# v2.net
KiCad netlist of a schematic drawn in EAGLE
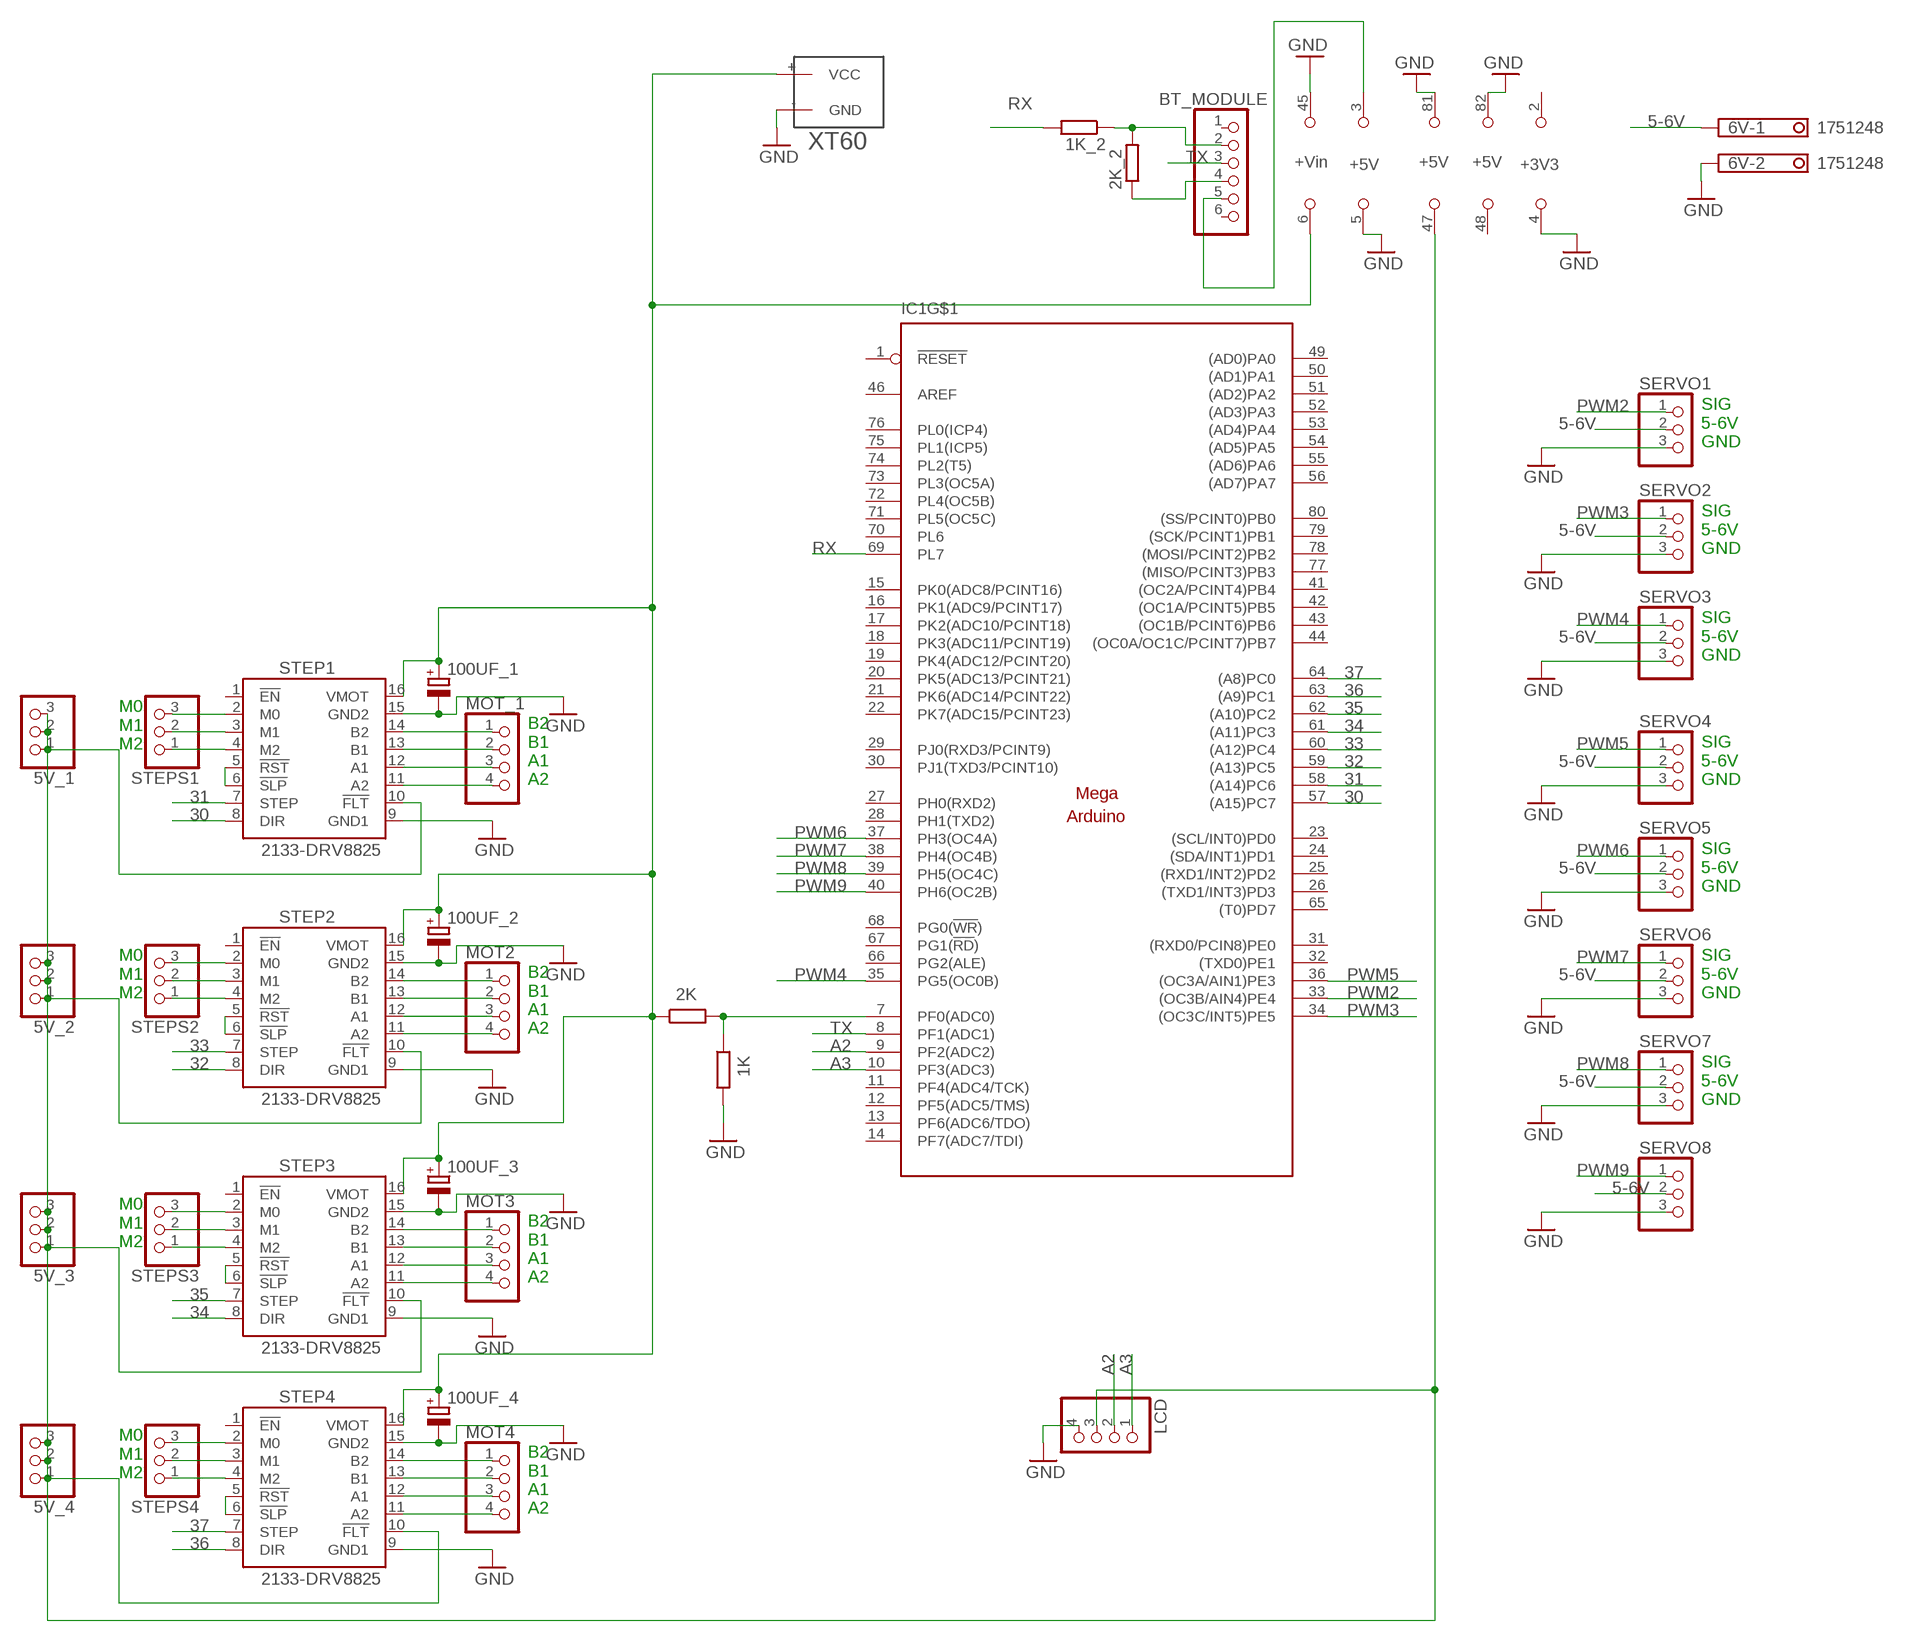
[diagram p0: schematic, sheet 1]

(export (version "E")
  (design (tool "Eeschema 10.0.6"))
  (components
    (comp (ref "1K")
      (value "R-EU_0204/7")
      (footprint "eagle-import:0204_7")
      (libsource (lib "eagle-import") (part "R-EU_0204/7"))
    )
    (comp (ref "1K_2")
      (value "R-EU_0204/7")
      (footprint "eagle-import:0204_7")
      (libsource (lib "eagle-import") (part "R-EU_0204/7"))
    )
    (comp (ref "2K")
      (value "R-EU_0204/7")
      (footprint "eagle-import:0204_7")
      (libsource (lib "eagle-import") (part "R-EU_0204/7"))
    )
    (comp (ref "2K_2")
      (value "R-EU_0204/7")
      (footprint "eagle-import:0204_7")
      (libsource (lib "eagle-import") (part "R-EU_0204/7"))
    )
    (comp (ref "5V_1")
      (value "PINHD-1X3")
      (footprint "eagle-import:1X03")
      (libsource (lib "eagle-import") (part "PINHD-1X3"))
    )
    (comp (ref "5V_2")
      (value "PINHD-1X3")
      (footprint "eagle-import:1X03")
      (libsource (lib "eagle-import") (part "PINHD-1X3"))
    )
    (comp (ref "5V_3")
      (value "PINHD-1X3")
      (footprint "eagle-import:1X03")
      (libsource (lib "eagle-import") (part "PINHD-1X3"))
    )
    (comp (ref "5V_4")
      (value "PINHD-1X3")
      (footprint "eagle-import:1X03")
      (libsource (lib "eagle-import") (part "PINHD-1X3"))
    )
    (comp (ref "6V")
      (value "1751248")
      (footprint "eagle-import:1751248")
      (libsource (lib "eagle-import") (part "1751248"))
    )
    (comp (ref "100UF_1")
      (value "CPOL-EUE5-5")
      (footprint "eagle-import:E5-5")
      (libsource (lib "eagle-import") (part "CPOL-EUE5-5"))
    )
    (comp (ref "100UF_2")
      (value "CPOL-EUE5-5")
      (footprint "eagle-import:E5-5")
      (libsource (lib "eagle-import") (part "CPOL-EUE5-5"))
    )
    (comp (ref "100UF_3")
      (value "CPOL-EUE5-5")
      (footprint "eagle-import:E5-5")
      (libsource (lib "eagle-import") (part "CPOL-EUE5-5"))
    )
    (comp (ref "100UF_4")
      (value "CPOL-EUE5-5")
      (footprint "eagle-import:E5-5")
      (libsource (lib "eagle-import") (part "CPOL-EUE5-5"))
    )
    (comp (ref "BT_MODULE")
      (value "PINHD-1X6")
      (footprint "eagle-import:1X06")
      (libsource (lib "eagle-import") (part "PINHD-1X6"))
    )
    (comp (ref "IC1")
      (value "MEGAARDUINO_22")
      (footprint "eagle-import:MEGA_ARDUINO_2")
      (libsource (lib "eagle-import") (part "MEGAARDUINO_22"))
    )
    (comp (ref "LCD")
      (value "PINHD-1X4")
      (footprint "eagle-import:1X04")
      (libsource (lib "eagle-import") (part "PINHD-1X4"))
    )
    (comp (ref "MOT2")
      (value "PINHD-1X4")
      (footprint "eagle-import:1X04")
      (libsource (lib "eagle-import") (part "PINHD-1X4"))
    )
    (comp (ref "MOT3")
      (value "PINHD-1X4")
      (footprint "eagle-import:1X04")
      (libsource (lib "eagle-import") (part "PINHD-1X4"))
    )
    (comp (ref "MOT4")
      (value "PINHD-1X4")
      (footprint "eagle-import:1X04")
      (libsource (lib "eagle-import") (part "PINHD-1X4"))
    )
    (comp (ref "MOT_1")
      (value "PINHD-1X4")
      (footprint "eagle-import:1X04")
      (libsource (lib "eagle-import") (part "PINHD-1X4"))
    )
    (comp (ref "SERVO1")
      (value "PINHD-1X3")
      (footprint "eagle-import:1X03")
      (libsource (lib "eagle-import") (part "PINHD-1X3"))
    )
    (comp (ref "SERVO2")
      (value "PINHD-1X3")
      (footprint "eagle-import:1X03")
      (libsource (lib "eagle-import") (part "PINHD-1X3"))
    )
    (comp (ref "SERVO3")
      (value "PINHD-1X3")
      (footprint "eagle-import:1X03")
      (libsource (lib "eagle-import") (part "PINHD-1X3"))
    )
    (comp (ref "SERVO4")
      (value "PINHD-1X3")
      (footprint "eagle-import:1X03")
      (libsource (lib "eagle-import") (part "PINHD-1X3"))
    )
    (comp (ref "SERVO5")
      (value "PINHD-1X3")
      (footprint "eagle-import:1X03")
      (libsource (lib "eagle-import") (part "PINHD-1X3"))
    )
    (comp (ref "SERVO6")
      (value "PINHD-1X3")
      (footprint "eagle-import:1X03")
      (libsource (lib "eagle-import") (part "PINHD-1X3"))
    )
    (comp (ref "SERVO7")
      (value "PINHD-1X3")
      (footprint "eagle-import:1X03")
      (libsource (lib "eagle-import") (part "PINHD-1X3"))
    )
    (comp (ref "SERVO8")
      (value "PINHD-1X3")
      (footprint "eagle-import:1X03")
      (libsource (lib "eagle-import") (part "PINHD-1X3"))
    )
    (comp (ref "STEP1")
      (value "2133-DRV8825")
      (footprint "eagle-import:DRV8825")
      (libsource (lib "eagle-import") (part "2133-DRV8825"))
    )
    (comp (ref "STEP2")
      (value "2133-DRV8825")
      (footprint "eagle-import:DRV8825")
      (libsource (lib "eagle-import") (part "2133-DRV8825"))
    )
    (comp (ref "STEP3")
      (value "2133-DRV8825")
      (footprint "eagle-import:DRV8825")
      (libsource (lib "eagle-import") (part "2133-DRV8825"))
    )
    (comp (ref "STEP4")
      (value "2133-DRV8825")
      (footprint "eagle-import:DRV8825")
      (libsource (lib "eagle-import") (part "2133-DRV8825"))
    )
    (comp (ref "STEPS1")
      (value "PINHD-1X3")
      (footprint "eagle-import:1X03")
      (libsource (lib "eagle-import") (part "PINHD-1X3"))
    )
    (comp (ref "STEPS2")
      (value "PINHD-1X3")
      (footprint "eagle-import:1X03")
      (libsource (lib "eagle-import") (part "PINHD-1X3"))
    )
    (comp (ref "STEPS3")
      (value "PINHD-1X3")
      (footprint "eagle-import:1X03")
      (libsource (lib "eagle-import") (part "PINHD-1X3"))
    )
    (comp (ref "STEPS4")
      (value "PINHD-1X3")
      (footprint "eagle-import:1X03")
      (libsource (lib "eagle-import") (part "PINHD-1X3"))
    )
    (comp (ref "U$1")
      (value "XT60")
      (footprint "eagle-import:XT60")
      (libsource (lib "eagle-import") (part "XT60"))
    )
  )
  (nets
    (net (code "1") (name "/+3V3") (class "Default")
      (node (ref "IC1") (pin "2") (pinfunction "+3V3_2") (pintype "power_in"))
    )
    (net (code "2") (name "/+5V") (class "Default")
      (node (ref "IC1") (pin "48") (pinfunction "+5V_48") (pintype "power_in"))
    )
    (net (code "3") (name "/5-6V") (class "Default")
      (node (ref "6V") (pin "1") (pinfunction "K_1") (pintype "passive"))
      (node (ref "SERVO1") (pin "2") (pinfunction "2_2") (pintype "passive"))
      (node (ref "SERVO2") (pin "2") (pinfunction "2_2") (pintype "passive"))
      (node (ref "SERVO3") (pin "2") (pinfunction "2_2") (pintype "passive"))
      (node (ref "SERVO4") (pin "2") (pinfunction "2_2") (pintype "passive"))
      (node (ref "SERVO5") (pin "2") (pinfunction "2_2") (pintype "passive"))
      (node (ref "SERVO6") (pin "2") (pinfunction "2_2") (pintype "passive"))
      (node (ref "SERVO7") (pin "2") (pinfunction "2_2") (pintype "passive"))
      (node (ref "SERVO8") (pin "2") (pinfunction "2_2") (pintype "passive"))
    )
    (net (code "4") (name "/30") (class "Default")
      (node (ref "IC1") (pin "57") (pinfunction "(A15)PC7_57") (pintype "bidirectional"))
      (node (ref "STEP1") (pin "8") (pinfunction "DIR_8") (pintype "input"))
    )
    (net (code "5") (name "/31") (class "Default")
      (node (ref "IC1") (pin "58") (pinfunction "(A14)PC6_58") (pintype "bidirectional"))
      (node (ref "STEP1") (pin "7") (pinfunction "STEP_7") (pintype "input"))
    )
    (net (code "6") (name "/32") (class "Default")
      (node (ref "IC1") (pin "59") (pinfunction "(A13)PC5_59") (pintype "bidirectional"))
      (node (ref "STEP2") (pin "8") (pinfunction "DIR_8") (pintype "input"))
    )
    (net (code "7") (name "/33") (class "Default")
      (node (ref "IC1") (pin "60") (pinfunction "(A12)PC4_60") (pintype "bidirectional"))
      (node (ref "STEP2") (pin "7") (pinfunction "STEP_7") (pintype "input"))
    )
    (net (code "8") (name "/34") (class "Default")
      (node (ref "IC1") (pin "61") (pinfunction "(A11)PC3_61") (pintype "bidirectional"))
      (node (ref "STEP3") (pin "8") (pinfunction "DIR_8") (pintype "input"))
    )
    (net (code "9") (name "/35") (class "Default")
      (node (ref "IC1") (pin "62") (pinfunction "(A10)PC2_62") (pintype "bidirectional"))
      (node (ref "STEP3") (pin "7") (pinfunction "STEP_7") (pintype "input"))
    )
    (net (code "10") (name "/36") (class "Default")
      (node (ref "IC1") (pin "63") (pinfunction "(A9)PC1_63") (pintype "bidirectional"))
      (node (ref "STEP4") (pin "8") (pinfunction "DIR_8") (pintype "input"))
    )
    (net (code "11") (name "/37") (class "Default")
      (node (ref "IC1") (pin "64") (pinfunction "(A8)PC0_64") (pintype "bidirectional"))
      (node (ref "STEP4") (pin "7") (pinfunction "STEP_7") (pintype "input"))
    )
    (net (code "12") (name "/A2") (class "Default")
      (node (ref "IC1") (pin "9") (pinfunction "PF2(ADC2)_9") (pintype "bidirectional"))
      (node (ref "LCD") (pin "2") (pinfunction "2_2") (pintype "passive"))
    )
    (net (code "13") (name "/A3") (class "Default")
      (node (ref "IC1") (pin "10") (pinfunction "PF3(ADC3)_10") (pintype "bidirectional"))
      (node (ref "LCD") (pin "1") (pinfunction "1_1") (pintype "passive"))
    )
    (net (code "14") (name "/PWM2") (class "Default")
      (node (ref "IC1") (pin "33") (pinfunction "(OC3B/AIN4)PE4_33") (pintype "bidirectional"))
      (node (ref "SERVO1") (pin "1") (pinfunction "1_1") (pintype "passive"))
    )
    (net (code "15") (name "/PWM3") (class "Default")
      (node (ref "IC1") (pin "34") (pinfunction "(OC3C/INT5)PE5_34") (pintype "bidirectional"))
      (node (ref "SERVO2") (pin "1") (pinfunction "1_1") (pintype "passive"))
    )
    (net (code "16") (name "/PWM4") (class "Default")
      (node (ref "IC1") (pin "35") (pinfunction "PG5(OC0B)_35") (pintype "bidirectional"))
      (node (ref "SERVO3") (pin "1") (pinfunction "1_1") (pintype "passive"))
    )
    (net (code "17") (name "/PWM5") (class "Default")
      (node (ref "IC1") (pin "36") (pinfunction "(OC3A/AIN1)PE3_36") (pintype "bidirectional"))
      (node (ref "SERVO4") (pin "1") (pinfunction "1_1") (pintype "passive"))
    )
    (net (code "18") (name "/PWM6") (class "Default")
      (node (ref "IC1") (pin "37") (pinfunction "PH3(OC4A)_37") (pintype "bidirectional"))
      (node (ref "SERVO5") (pin "1") (pinfunction "1_1") (pintype "passive"))
    )
    (net (code "19") (name "/PWM7") (class "Default")
      (node (ref "IC1") (pin "38") (pinfunction "PH4(OC4B)_38") (pintype "bidirectional"))
      (node (ref "SERVO6") (pin "1") (pinfunction "1_1") (pintype "passive"))
    )
    (net (code "20") (name "/PWM8") (class "Default")
      (node (ref "IC1") (pin "39") (pinfunction "PH5(OC4C)_39") (pintype "bidirectional"))
      (node (ref "SERVO7") (pin "1") (pinfunction "1_1") (pintype "passive"))
    )
    (net (code "21") (name "/PWM9") (class "Default")
      (node (ref "IC1") (pin "40") (pinfunction "PH6(OC2B)_40") (pintype "bidirectional"))
      (node (ref "SERVO8") (pin "1") (pinfunction "1_1") (pintype "passive"))
    )
    (net (code "22") (name "/RX") (class "Default")
      (node (ref "1K_2") (pin "2") (pinfunction "2_2") (pintype "passive"))
      (node (ref "IC1") (pin "69") (pinfunction "PL7_69") (pintype "bidirectional"))
    )
    (net (code "23") (name "/TX") (class "Default")
      (node (ref "BT_MODULE") (pin "3") (pinfunction "3_3") (pintype "passive"))
      (node (ref "IC1") (pin "8") (pinfunction "PF1(ADC1)_8") (pintype "bidirectional"))
    )
    (net (code "24") (name "GND") (class "Default")
      (node (ref "100UF_1") (pin "-") (pinfunction "-_-") (pintype "passive"))
      (node (ref "100UF_2") (pin "-") (pinfunction "-_-") (pintype "passive"))
      (node (ref "100UF_3") (pin "-") (pinfunction "-_-") (pintype "passive"))
      (node (ref "100UF_4") (pin "-") (pinfunction "-_-") (pintype "passive"))
      (node (ref "1K") (pin "2") (pinfunction "2_2") (pintype "passive"))
      (node (ref "6V") (pin "2") (pinfunction "K_2") (pintype "passive"))
      (node (ref "IC1") (pin "4") (pinfunction "GND_4") (pintype "power_in"))
      (node (ref "IC1") (pin "45") (pinfunction "GND_45") (pintype "power_in"))
      (node (ref "IC1") (pin "5") (pinfunction "GND_5") (pintype "power_in"))
      (node (ref "IC1") (pin "81") (pinfunction "GND_81") (pintype "power_in"))
      (node (ref "IC1") (pin "82") (pinfunction "GND_82") (pintype "power_in"))
      (node (ref "LCD") (pin "4") (pinfunction "4_4") (pintype "passive"))
      (node (ref "SERVO1") (pin "3") (pinfunction "3_3") (pintype "passive"))
      (node (ref "SERVO2") (pin "3") (pinfunction "3_3") (pintype "passive"))
      (node (ref "SERVO3") (pin "3") (pinfunction "3_3") (pintype "passive"))
      (node (ref "SERVO4") (pin "3") (pinfunction "3_3") (pintype "passive"))
      (node (ref "SERVO5") (pin "3") (pinfunction "3_3") (pintype "passive"))
      (node (ref "SERVO6") (pin "3") (pinfunction "3_3") (pintype "passive"))
      (node (ref "SERVO7") (pin "3") (pinfunction "3_3") (pintype "passive"))
      (node (ref "SERVO8") (pin "3") (pinfunction "3_3") (pintype "passive"))
      (node (ref "STEP1") (pin "15") (pinfunction "GND2_15") (pintype "power_in"))
      (node (ref "STEP1") (pin "9") (pinfunction "GND1_9") (pintype "power_in"))
      (node (ref "STEP2") (pin "15") (pinfunction "GND2_15") (pintype "power_in"))
      (node (ref "STEP2") (pin "9") (pinfunction "GND1_9") (pintype "power_in"))
      (node (ref "STEP3") (pin "15") (pinfunction "GND2_15") (pintype "power_in"))
      (node (ref "STEP3") (pin "9") (pinfunction "GND1_9") (pintype "power_in"))
      (node (ref "STEP4") (pin "15") (pinfunction "GND2_15") (pintype "power_in"))
      (node (ref "STEP4") (pin "9") (pinfunction "GND1_9") (pintype "power_in"))
      (node (ref "U$1") (pin "-") (pinfunction "GND_-") (pintype "bidirectional"))
    )
    (net (code "25") (name "Net-(1K_2-Pad1)") (class "Default")
      (node (ref "1K_2") (pin "1") (pinfunction "1_1") (pintype "passive"))
      (node (ref "2K_2") (pin "2") (pinfunction "2_2") (pintype "passive"))
      (node (ref "BT_MODULE") (pin "2") (pinfunction "2_2") (pintype "passive"))
    )
    (net (code "26") (name "Net-(2K_2-Pad1)") (class "Default")
      (node (ref "2K_2") (pin "1") (pinfunction "1_1") (pintype "passive"))
      (node (ref "BT_MODULE") (pin "4") (pinfunction "4_4") (pintype "passive"))
    )
    (net (code "27") (name "Net-(IC1A-PF0(ADC0))") (class "Default")
      (node (ref "1K") (pin "1") (pinfunction "1_1") (pintype "passive"))
      (node (ref "2K") (pin "2") (pinfunction "2_2") (pintype "passive"))
      (node (ref "IC1") (pin "7") (pinfunction "PF0(ADC0)_7") (pintype "bidirectional"))
    )
    (net (code "28") (name "Net-(IC1B-+5V)") (class "Default")
      (node (ref "BT_MODULE") (pin "5") (pinfunction "5_5") (pintype "passive"))
      (node (ref "IC1") (pin "3") (pinfunction "+5V_3") (pintype "power_in"))
    )
    (net (code "29") (name "Net-(IC1C-+5V)") (class "Default")
      (node (ref "5V_1") (pin "1") (pinfunction "1_1") (pintype "passive"))
      (node (ref "5V_1") (pin "2") (pinfunction "2_2") (pintype "passive"))
      (node (ref "5V_1") (pin "3") (pinfunction "3_3") (pintype "passive"))
      (node (ref "5V_2") (pin "1") (pinfunction "1_1") (pintype "passive"))
      (node (ref "5V_2") (pin "2") (pinfunction "2_2") (pintype "passive"))
      (node (ref "5V_2") (pin "3") (pinfunction "3_3") (pintype "passive"))
      (node (ref "5V_3") (pin "1") (pinfunction "1_1") (pintype "passive"))
      (node (ref "5V_3") (pin "2") (pinfunction "2_2") (pintype "passive"))
      (node (ref "5V_3") (pin "3") (pinfunction "3_3") (pintype "passive"))
      (node (ref "5V_4") (pin "1") (pinfunction "1_1") (pintype "passive"))
      (node (ref "5V_4") (pin "2") (pinfunction "2_2") (pintype "passive"))
      (node (ref "5V_4") (pin "3") (pinfunction "3_3") (pintype "passive"))
      (node (ref "IC1") (pin "47") (pinfunction "+5V_47") (pintype "power_in"))
      (node (ref "LCD") (pin "3") (pinfunction "3_3") (pintype "passive"))
      (node (ref "STEP1") (pin "10") (pinfunction "~{FLT}_10") (pintype "open_collector"))
      (node (ref "STEP2") (pin "10") (pinfunction "~{FLT}_10") (pintype "open_collector"))
      (node (ref "STEP3") (pin "10") (pinfunction "~{FLT}_10") (pintype "open_collector"))
      (node (ref "STEP4") (pin "10") (pinfunction "~{FLT}_10") (pintype "open_collector"))
    )
    (net (code "30") (name "Net-(IC1F-+VIN)") (class "Default")
      (node (ref "100UF_1") (pin "+") (pinfunction "+_+") (pintype "passive"))
      (node (ref "100UF_2") (pin "+") (pinfunction "+_+") (pintype "passive"))
      (node (ref "100UF_3") (pin "+") (pinfunction "+_+") (pintype "passive"))
      (node (ref "100UF_4") (pin "+") (pinfunction "+_+") (pintype "passive"))
      (node (ref "2K") (pin "1") (pinfunction "1_1") (pintype "passive"))
      (node (ref "IC1") (pin "6") (pinfunction "+VIN_6") (pintype "power_in"))
      (node (ref "STEP1") (pin "16") (pinfunction "VMOT_16") (pintype "power_in"))
      (node (ref "STEP2") (pin "16") (pinfunction "VMOT_16") (pintype "power_in"))
      (node (ref "STEP3") (pin "16") (pinfunction "VMOT_16") (pintype "power_in"))
      (node (ref "STEP4") (pin "16") (pinfunction "VMOT_16") (pintype "power_in"))
      (node (ref "U$1") (pin "+") (pinfunction "VCC_+") (pintype "bidirectional"))
    )
    (net (code "31") (name "Net-(STEP1-A1)") (class "Default")
      (node (ref "MOT_1") (pin "3") (pinfunction "3_3") (pintype "passive"))
      (node (ref "STEP1") (pin "12") (pinfunction "A1_12") (pintype "output"))
    )
    (net (code "32") (name "Net-(STEP1-A2)") (class "Default")
      (node (ref "MOT_1") (pin "4") (pinfunction "4_4") (pintype "passive"))
      (node (ref "STEP1") (pin "11") (pinfunction "A2_11") (pintype "output"))
    )
    (net (code "33") (name "Net-(STEP1-B1)") (class "Default")
      (node (ref "MOT_1") (pin "2") (pinfunction "2_2") (pintype "passive"))
      (node (ref "STEP1") (pin "13") (pinfunction "B1_13") (pintype "output"))
    )
    (net (code "34") (name "Net-(STEP1-B2)") (class "Default")
      (node (ref "MOT_1") (pin "1") (pinfunction "1_1") (pintype "passive"))
      (node (ref "STEP1") (pin "14") (pinfunction "B2_14") (pintype "output"))
    )
    (net (code "35") (name "Net-(STEP1-M0)") (class "Default")
      (node (ref "STEP1") (pin "2") (pinfunction "M0_2") (pintype "passive"))
      (node (ref "STEPS1") (pin "3") (pinfunction "3_3") (pintype "passive"))
    )
    (net (code "36") (name "Net-(STEP1-M1)") (class "Default")
      (node (ref "STEP1") (pin "3") (pinfunction "M1_3") (pintype "passive"))
      (node (ref "STEPS1") (pin "2") (pinfunction "2_2") (pintype "passive"))
    )
    (net (code "37") (name "Net-(STEP1-M2)") (class "Default")
      (node (ref "STEP1") (pin "4") (pinfunction "M2_4") (pintype "passive"))
      (node (ref "STEPS1") (pin "1") (pinfunction "1_1") (pintype "passive"))
    )
    (net (code "38") (name "Net-(STEP1-~{RST})") (class "Default")
      (node (ref "STEP1") (pin "5") (pinfunction "~{RST}_5") (pintype "input"))
      (node (ref "STEP1") (pin "6") (pinfunction "~{SLP}_6") (pintype "input"))
    )
    (net (code "39") (name "Net-(STEP2-A1)") (class "Default")
      (node (ref "MOT2") (pin "3") (pinfunction "3_3") (pintype "passive"))
      (node (ref "STEP2") (pin "12") (pinfunction "A1_12") (pintype "output"))
    )
    (net (code "40") (name "Net-(STEP2-A2)") (class "Default")
      (node (ref "MOT2") (pin "4") (pinfunction "4_4") (pintype "passive"))
      (node (ref "STEP2") (pin "11") (pinfunction "A2_11") (pintype "output"))
    )
    (net (code "41") (name "Net-(STEP2-B1)") (class "Default")
      (node (ref "MOT2") (pin "2") (pinfunction "2_2") (pintype "passive"))
      (node (ref "STEP2") (pin "13") (pinfunction "B1_13") (pintype "output"))
    )
    (net (code "42") (name "Net-(STEP2-B2)") (class "Default")
      (node (ref "MOT2") (pin "1") (pinfunction "1_1") (pintype "passive"))
      (node (ref "STEP2") (pin "14") (pinfunction "B2_14") (pintype "output"))
    )
    (net (code "43") (name "Net-(STEP2-M0)") (class "Default")
      (node (ref "STEP2") (pin "2") (pinfunction "M0_2") (pintype "passive"))
      (node (ref "STEPS2") (pin "3") (pinfunction "3_3") (pintype "passive"))
    )
    (net (code "44") (name "Net-(STEP2-M1)") (class "Default")
      (node (ref "STEP2") (pin "3") (pinfunction "M1_3") (pintype "passive"))
      (node (ref "STEPS2") (pin "2") (pinfunction "2_2") (pintype "passive"))
    )
    (net (code "45") (name "Net-(STEP2-M2)") (class "Default")
      (node (ref "STEP2") (pin "4") (pinfunction "M2_4") (pintype "passive"))
      (node (ref "STEPS2") (pin "1") (pinfunction "1_1") (pintype "passive"))
    )
    (net (code "46") (name "Net-(STEP2-~{RST})") (class "Default")
      (node (ref "STEP2") (pin "5") (pinfunction "~{RST}_5") (pintype "input"))
      (node (ref "STEP2") (pin "6") (pinfunction "~{SLP}_6") (pintype "input"))
    )
    (net (code "47") (name "Net-(STEP3-A1)") (class "Default")
      (node (ref "MOT3") (pin "3") (pinfunction "3_3") (pintype "passive"))
      (node (ref "STEP3") (pin "12") (pinfunction "A1_12") (pintype "output"))
    )
    (net (code "48") (name "Net-(STEP3-A2)") (class "Default")
      (node (ref "MOT3") (pin "4") (pinfunction "4_4") (pintype "passive"))
      (node (ref "STEP3") (pin "11") (pinfunction "A2_11") (pintype "output"))
    )
    (net (code "49") (name "Net-(STEP3-B1)") (class "Default")
      (node (ref "MOT3") (pin "2") (pinfunction "2_2") (pintype "passive"))
      (node (ref "STEP3") (pin "13") (pinfunction "B1_13") (pintype "output"))
    )
    (net (code "50") (name "Net-(STEP3-B2)") (class "Default")
      (node (ref "MOT3") (pin "1") (pinfunction "1_1") (pintype "passive"))
      (node (ref "STEP3") (pin "14") (pinfunction "B2_14") (pintype "output"))
    )
    (net (code "51") (name "Net-(STEP3-M0)") (class "Default")
      (node (ref "STEP3") (pin "2") (pinfunction "M0_2") (pintype "passive"))
      (node (ref "STEPS3") (pin "3") (pinfunction "3_3") (pintype "passive"))
    )
    (net (code "52") (name "Net-(STEP3-M1)") (class "Default")
      (node (ref "STEP3") (pin "3") (pinfunction "M1_3") (pintype "passive"))
      (node (ref "STEPS3") (pin "2") (pinfunction "2_2") (pintype "passive"))
    )
    (net (code "53") (name "Net-(STEP3-M2)") (class "Default")
      (node (ref "STEP3") (pin "4") (pinfunction "M2_4") (pintype "passive"))
      (node (ref "STEPS3") (pin "1") (pinfunction "1_1") (pintype "passive"))
    )
    (net (code "54") (name "Net-(STEP3-~{RST})") (class "Default")
      (node (ref "STEP3") (pin "5") (pinfunction "~{RST}_5") (pintype "input"))
      (node (ref "STEP3") (pin "6") (pinfunction "~{SLP}_6") (pintype "input"))
    )
    (net (code "55") (name "Net-(STEP4-A1)") (class "Default")
      (node (ref "MOT4") (pin "3") (pinfunction "3_3") (pintype "passive"))
      (node (ref "STEP4") (pin "12") (pinfunction "A1_12") (pintype "output"))
    )
    (net (code "56") (name "Net-(STEP4-A2)") (class "Default")
      (node (ref "MOT4") (pin "4") (pinfunction "4_4") (pintype "passive"))
      (node (ref "STEP4") (pin "11") (pinfunction "A2_11") (pintype "output"))
    )
    (net (code "57") (name "Net-(STEP4-B1)") (class "Default")
      (node (ref "MOT4") (pin "2") (pinfunction "2_2") (pintype "passive"))
      (node (ref "STEP4") (pin "13") (pinfunction "B1_13") (pintype "output"))
    )
    (net (code "58") (name "Net-(STEP4-B2)") (class "Default")
      (node (ref "MOT4") (pin "1") (pinfunction "1_1") (pintype "passive"))
      (node (ref "STEP4") (pin "14") (pinfunction "B2_14") (pintype "output"))
    )
    (net (code "59") (name "Net-(STEP4-M0)") (class "Default")
      (node (ref "STEP4") (pin "2") (pinfunction "M0_2") (pintype "passive"))
      (node (ref "STEPS4") (pin "3") (pinfunction "3_3") (pintype "passive"))
    )
    (net (code "60") (name "Net-(STEP4-M1)") (class "Default")
      (node (ref "STEP4") (pin "3") (pinfunction "M1_3") (pintype "passive"))
      (node (ref "STEPS4") (pin "2") (pinfunction "2_2") (pintype "passive"))
    )
    (net (code "61") (name "Net-(STEP4-M2)") (class "Default")
      (node (ref "STEP4") (pin "4") (pinfunction "M2_4") (pintype "passive"))
      (node (ref "STEPS4") (pin "1") (pinfunction "1_1") (pintype "passive"))
    )
    (net (code "62") (name "Net-(STEP4-~{RST})") (class "Default")
      (node (ref "STEP4") (pin "5") (pinfunction "~{RST}_5") (pintype "input"))
      (node (ref "STEP4") (pin "6") (pinfunction "~{SLP}_6") (pintype "input"))
    )
    (net (code "63") (name "unconnected-(BT_MODULE-Pad1)") (class "Default")
      (node (ref "BT_MODULE") (pin "1") (pinfunction "1_1") (pintype "passive"))
    )
    (net (code "64") (name "unconnected-(BT_MODULE-Pad6)") (class "Default")
      (node (ref "BT_MODULE") (pin "6") (pinfunction "6_6") (pintype "passive"))
    )
    (net (code "65") (name "unconnected-(IC1A-(AD0)PA0-Pad49)") (class "Default")
      (node (ref "IC1") (pin "49") (pinfunction "(AD0)PA0_49") (pintype "bidirectional"))
    )
    (net (code "66") (name "unconnected-(IC1A-(AD1)PA1-Pad50)") (class "Default")
      (node (ref "IC1") (pin "50") (pinfunction "(AD1)PA1_50") (pintype "bidirectional"))
    )
    (net (code "67") (name "unconnected-(IC1A-(AD2)PA2-Pad51)") (class "Default")
      (node (ref "IC1") (pin "51") (pinfunction "(AD2)PA2_51") (pintype "bidirectional"))
    )
    (net (code "68") (name "unconnected-(IC1A-(AD3)PA3-Pad52)") (class "Default")
      (node (ref "IC1") (pin "52") (pinfunction "(AD3)PA3_52") (pintype "bidirectional"))
    )
    (net (code "69") (name "unconnected-(IC1A-(AD4)PA4-Pad53)") (class "Default")
      (node (ref "IC1") (pin "53") (pinfunction "(AD4)PA4_53") (pintype "bidirectional"))
    )
    (net (code "70") (name "unconnected-(IC1A-(AD5)PA5-Pad54)") (class "Default")
      (node (ref "IC1") (pin "54") (pinfunction "(AD5)PA5_54") (pintype "bidirectional"))
    )
    (net (code "71") (name "unconnected-(IC1A-(AD6)PA6-Pad55)") (class "Default")
      (node (ref "IC1") (pin "55") (pinfunction "(AD6)PA6_55") (pintype "bidirectional"))
    )
    (net (code "72") (name "unconnected-(IC1A-(AD7)PA7-Pad56)") (class "Default")
      (node (ref "IC1") (pin "56") (pinfunction "(AD7)PA7_56") (pintype "bidirectional"))
    )
    (net (code "73") (name "unconnected-(IC1A-(MISO{slash}PCINT3)PB3-Pad77)") (class "Default")
      (node (ref "IC1") (pin "77") (pinfunction "(MISO/PCINT3)PB3_77") (pintype "bidirectional"))
    )
    (net (code "74") (name "unconnected-(IC1A-(MOSI{slash}PCINT2)PB2-Pad78)") (class "Default")
      (node (ref "IC1") (pin "78") (pinfunction "(MOSI/PCINT2)PB2_78") (pintype "bidirectional"))
    )
    (net (code "75") (name "unconnected-(IC1A-(OC0A{slash}OC1C{slash}PCINT7)PB7-Pad44)") (class "Default")
      (node (ref "IC1") (pin "44") (pinfunction "(OC0A/OC1C/PCINT7)PB7_44") (pintype "bidirectional"))
    )
    (net (code "76") (name "unconnected-(IC1A-(OC1A{slash}PCINT5)PB5-Pad42)") (class "Default")
      (node (ref "IC1") (pin "42") (pinfunction "(OC1A/PCINT5)PB5_42") (pintype "bidirectional"))
    )
    (net (code "77") (name "unconnected-(IC1A-(OC1B{slash}PCINT6)PB6-Pad43)") (class "Default")
      (node (ref "IC1") (pin "43") (pinfunction "(OC1B/PCINT6)PB6_43") (pintype "bidirectional"))
    )
    (net (code "78") (name "unconnected-(IC1A-(OC2A{slash}PCINT4)PB4-Pad41)") (class "Default")
      (node (ref "IC1") (pin "41") (pinfunction "(OC2A/PCINT4)PB4_41") (pintype "bidirectional"))
    )
    (net (code "79") (name "unconnected-(IC1A-(RXD0{slash}PCIN8)PE0-Pad31)") (class "Default")
      (node (ref "IC1") (pin "31") (pinfunction "(RXD0/PCIN8)PE0_31") (pintype "bidirectional"))
    )
    (net (code "80") (name "unconnected-(IC1A-(RXD1{slash}INT2)PD2-Pad25)") (class "Default")
      (node (ref "IC1") (pin "25") (pinfunction "(RXD1/INT2)PD2_25") (pintype "bidirectional"))
    )
    (net (code "81") (name "unconnected-(IC1A-(SCK{slash}PCINT1)PB1-Pad79)") (class "Default")
      (node (ref "IC1") (pin "79") (pinfunction "(SCK/PCINT1)PB1_79") (pintype "bidirectional"))
    )
    (net (code "82") (name "unconnected-(IC1A-(SCL{slash}INT0)PD0-Pad23)") (class "Default")
      (node (ref "IC1") (pin "23") (pinfunction "(SCL/INT0)PD0_23") (pintype "bidirectional"))
    )
    (net (code "83") (name "unconnected-(IC1A-(SDA{slash}INT1)PD1-Pad24)") (class "Default")
      (node (ref "IC1") (pin "24") (pinfunction "(SDA/INT1)PD1_24") (pintype "bidirectional"))
    )
    (net (code "84") (name "unconnected-(IC1A-(SS{slash}PCINT0)PB0-Pad80)") (class "Default")
      (node (ref "IC1") (pin "80") (pinfunction "(SS/PCINT0)PB0_80") (pintype "bidirectional"))
    )
    (net (code "85") (name "unconnected-(IC1A-(T0)PD7-Pad65)") (class "Default")
      (node (ref "IC1") (pin "65") (pinfunction "(T0)PD7_65") (pintype "bidirectional"))
    )
    (net (code "86") (name "unconnected-(IC1A-(TXD0)PE1-Pad32)") (class "Default")
      (node (ref "IC1") (pin "32") (pinfunction "(TXD0)PE1_32") (pintype "bidirectional"))
    )
    (net (code "87") (name "unconnected-(IC1A-(TXD1{slash}INT3)PD3-Pad26)") (class "Default")
      (node (ref "IC1") (pin "26") (pinfunction "(TXD1/INT3)PD3_26") (pintype "bidirectional"))
    )
    (net (code "88") (name "unconnected-(IC1A-AREF-Pad46)") (class "Default")
      (node (ref "IC1") (pin "46") (pinfunction "AREF_46") (pintype "bidirectional"))
    )
    (net (code "89") (name "unconnected-(IC1A-PF4(ADC4{slash}TCK)-Pad11)") (class "Default")
      (node (ref "IC1") (pin "11") (pinfunction "PF4(ADC4/TCK)_11") (pintype "bidirectional"))
    )
    (net (code "90") (name "unconnected-(IC1A-PF5(ADC5{slash}TMS)-Pad12)") (class "Default")
      (node (ref "IC1") (pin "12") (pinfunction "PF5(ADC5/TMS)_12") (pintype "bidirectional"))
    )
    (net (code "91") (name "unconnected-(IC1A-PF6(ADC6{slash}TDO)-Pad13)") (class "Default")
      (node (ref "IC1") (pin "13") (pinfunction "PF6(ADC6/TDO)_13") (pintype "bidirectional"))
    )
    (net (code "92") (name "unconnected-(IC1A-PF7(ADC7{slash}TDI)-Pad14)") (class "Default")
      (node (ref "IC1") (pin "14") (pinfunction "PF7(ADC7/TDI)_14") (pintype "bidirectional"))
    )
    (net (code "93") (name "unconnected-(IC1A-PG0(~{WR})-Pad68)") (class "Default")
      (node (ref "IC1") (pin "68") (pinfunction "PG0(~{WR})_68") (pintype "bidirectional"))
    )
    (net (code "94") (name "unconnected-(IC1A-PG1(~{RD})-Pad67)") (class "Default")
      (node (ref "IC1") (pin "67") (pinfunction "PG1(~{RD})_67") (pintype "bidirectional"))
    )
    (net (code "95") (name "unconnected-(IC1A-PG2(ALE)-Pad66)") (class "Default")
      (node (ref "IC1") (pin "66") (pinfunction "PG2(ALE)_66") (pintype "bidirectional"))
    )
    (net (code "96") (name "unconnected-(IC1A-PH0(RXD2)-Pad27)") (class "Default")
      (node (ref "IC1") (pin "27") (pinfunction "PH0(RXD2)_27") (pintype "bidirectional"))
    )
    (net (code "97") (name "unconnected-(IC1A-PH1(TXD2)-Pad28)") (class "Default")
      (node (ref "IC1") (pin "28") (pinfunction "PH1(TXD2)_28") (pintype "bidirectional"))
    )
    (net (code "98") (name "unconnected-(IC1A-PJ0(RXD3{slash}PCINT9)-Pad29)") (class "Default")
      (node (ref "IC1") (pin "29") (pinfunction "PJ0(RXD3/PCINT9)_29") (pintype "bidirectional"))
    )
    (net (code "99") (name "unconnected-(IC1A-PJ1(TXD3{slash}PCINT10)-Pad30)") (class "Default")
      (node (ref "IC1") (pin "30") (pinfunction "PJ1(TXD3/PCINT10)_30") (pintype "bidirectional"))
    )
    (net (code "100") (name "unconnected-(IC1A-PK0(ADC8{slash}PCINT16)-Pad15)") (class "Default")
      (node (ref "IC1") (pin "15") (pinfunction "PK0(ADC8/PCINT16)_15") (pintype "bidirectional"))
    )
    (net (code "101") (name "unconnected-(IC1A-PK1(ADC9{slash}PCINT17)-Pad16)") (class "Default")
      (node (ref "IC1") (pin "16") (pinfunction "PK1(ADC9/PCINT17)_16") (pintype "bidirectional"))
    )
    (net (code "102") (name "unconnected-(IC1A-PK2(ADC10{slash}PCINT18)-Pad17)") (class "Default")
      (node (ref "IC1") (pin "17") (pinfunction "PK2(ADC10/PCINT18)_17") (pintype "bidirectional"))
    )
    (net (code "103") (name "unconnected-(IC1A-PK3(ADC11{slash}PCINT19)-Pad18)") (class "Default")
      (node (ref "IC1") (pin "18") (pinfunction "PK3(ADC11/PCINT19)_18") (pintype "bidirectional"))
    )
    (net (code "104") (name "unconnected-(IC1A-PK4(ADC12{slash}PCINT20)-Pad19)") (class "Default")
      (node (ref "IC1") (pin "19") (pinfunction "PK4(ADC12/PCINT20)_19") (pintype "bidirectional"))
    )
    (net (code "105") (name "unconnected-(IC1A-PK5(ADC13{slash}PCINT21)-Pad20)") (class "Default")
      (node (ref "IC1") (pin "20") (pinfunction "PK5(ADC13/PCINT21)_20") (pintype "bidirectional"))
    )
    (net (code "106") (name "unconnected-(IC1A-PK6(ADC14{slash}PCINT22)-Pad21)") (class "Default")
      (node (ref "IC1") (pin "21") (pinfunction "PK6(ADC14/PCINT22)_21") (pintype "bidirectional"))
    )
    (net (code "107") (name "unconnected-(IC1A-PK7(ADC15{slash}PCINT23)-Pad22)") (class "Default")
      (node (ref "IC1") (pin "22") (pinfunction "PK7(ADC15/PCINT23)_22") (pintype "bidirectional"))
    )
    (net (code "108") (name "unconnected-(IC1A-PL0(ICP4)-Pad76)") (class "Default")
      (node (ref "IC1") (pin "76") (pinfunction "PL0(ICP4)_76") (pintype "bidirectional"))
    )
    (net (code "109") (name "unconnected-(IC1A-PL1(ICP5)-Pad75)") (class "Default")
      (node (ref "IC1") (pin "75") (pinfunction "PL1(ICP5)_75") (pintype "bidirectional"))
    )
    (net (code "110") (name "unconnected-(IC1A-PL2(T5)-Pad74)") (class "Default")
      (node (ref "IC1") (pin "74") (pinfunction "PL2(T5)_74") (pintype "bidirectional"))
    )
    (net (code "111") (name "unconnected-(IC1A-PL3(OC5A)-Pad73)") (class "Default")
      (node (ref "IC1") (pin "73") (pinfunction "PL3(OC5A)_73") (pintype "bidirectional"))
    )
    (net (code "112") (name "unconnected-(IC1A-PL4(OC5B)-Pad72)") (class "Default")
      (node (ref "IC1") (pin "72") (pinfunction "PL4(OC5B)_72") (pintype "bidirectional"))
    )
    (net (code "113") (name "unconnected-(IC1A-PL5(OC5C)-Pad71)") (class "Default")
      (node (ref "IC1") (pin "71") (pinfunction "PL5(OC5C)_71") (pintype "bidirectional"))
    )
    (net (code "114") (name "unconnected-(IC1A-PL6-Pad70)") (class "Default")
      (node (ref "IC1") (pin "70") (pinfunction "PL6_70") (pintype "bidirectional"))
    )
    (net (code "115") (name "unconnected-(IC1A-~{RESET}-Pad1)") (class "Default")
      (node (ref "IC1") (pin "1") (pinfunction "~{RESET}_1") (pintype "bidirectional"))
    )
    (net (code "116") (name "unconnected-(STEP1-~{EN}-Pad1)") (class "Default")
      (node (ref "STEP1") (pin "1") (pinfunction "~{EN}_1") (pintype "passive"))
    )
    (net (code "117") (name "unconnected-(STEP2-~{EN}-Pad1)") (class "Default")
      (node (ref "STEP2") (pin "1") (pinfunction "~{EN}_1") (pintype "passive"))
    )
    (net (code "118") (name "unconnected-(STEP3-~{EN}-Pad1)") (class "Default")
      (node (ref "STEP3") (pin "1") (pinfunction "~{EN}_1") (pintype "passive"))
    )
    (net (code "119") (name "unconnected-(STEP4-~{EN}-Pad1)") (class "Default")
      (node (ref "STEP4") (pin "1") (pinfunction "~{EN}_1") (pintype "passive"))
    )
  )
)
